# ProProject_Laser_Scanner_Logic_converter.net
KiCad netlist of a schematic drawn in EasyEDA Pro
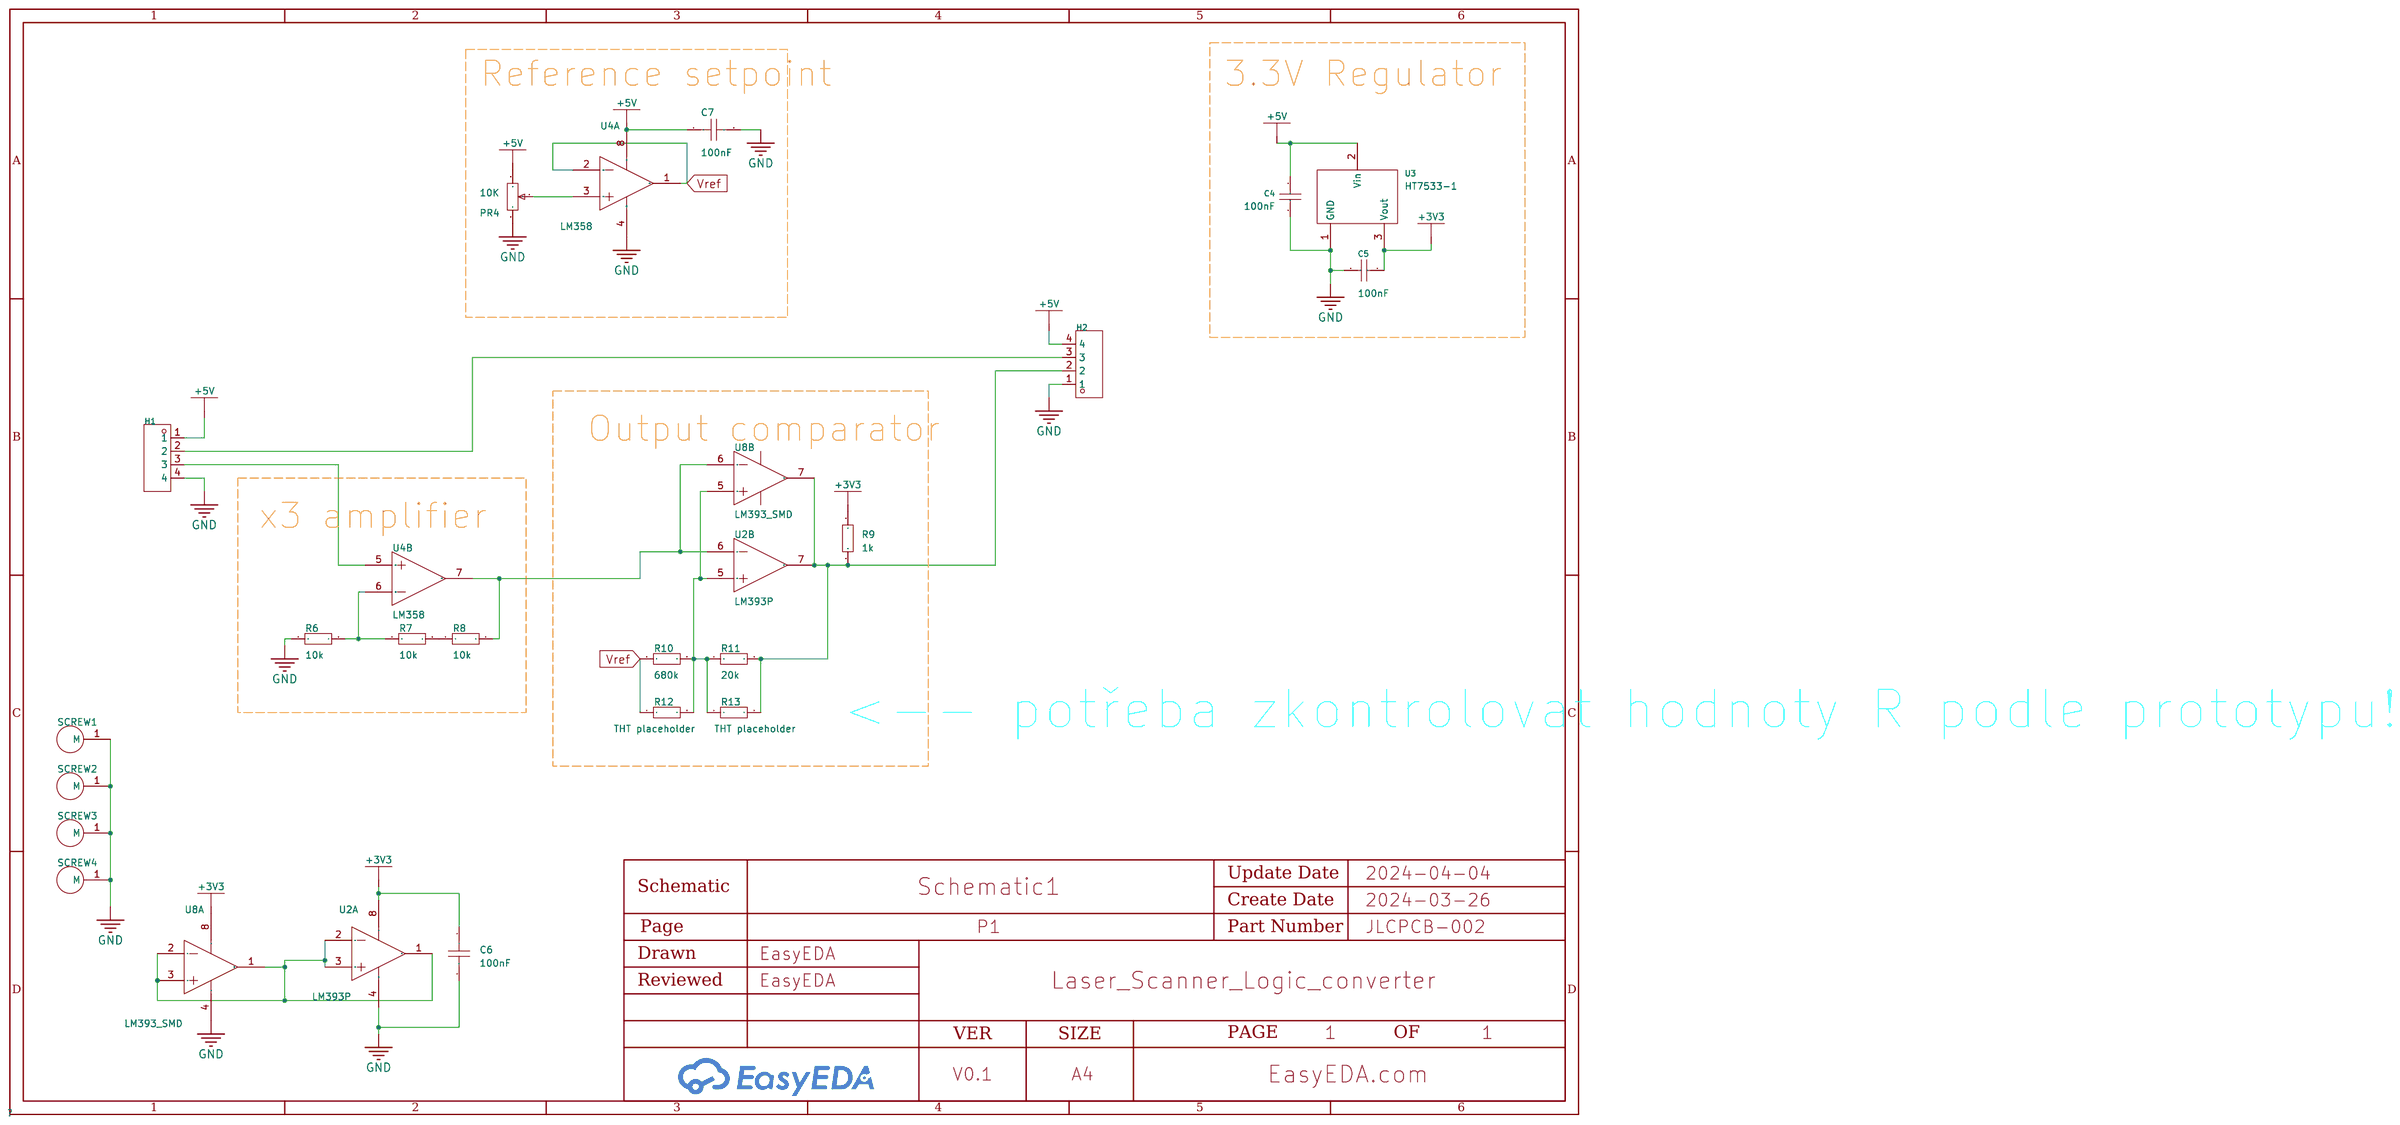
[diagram p0: P1]
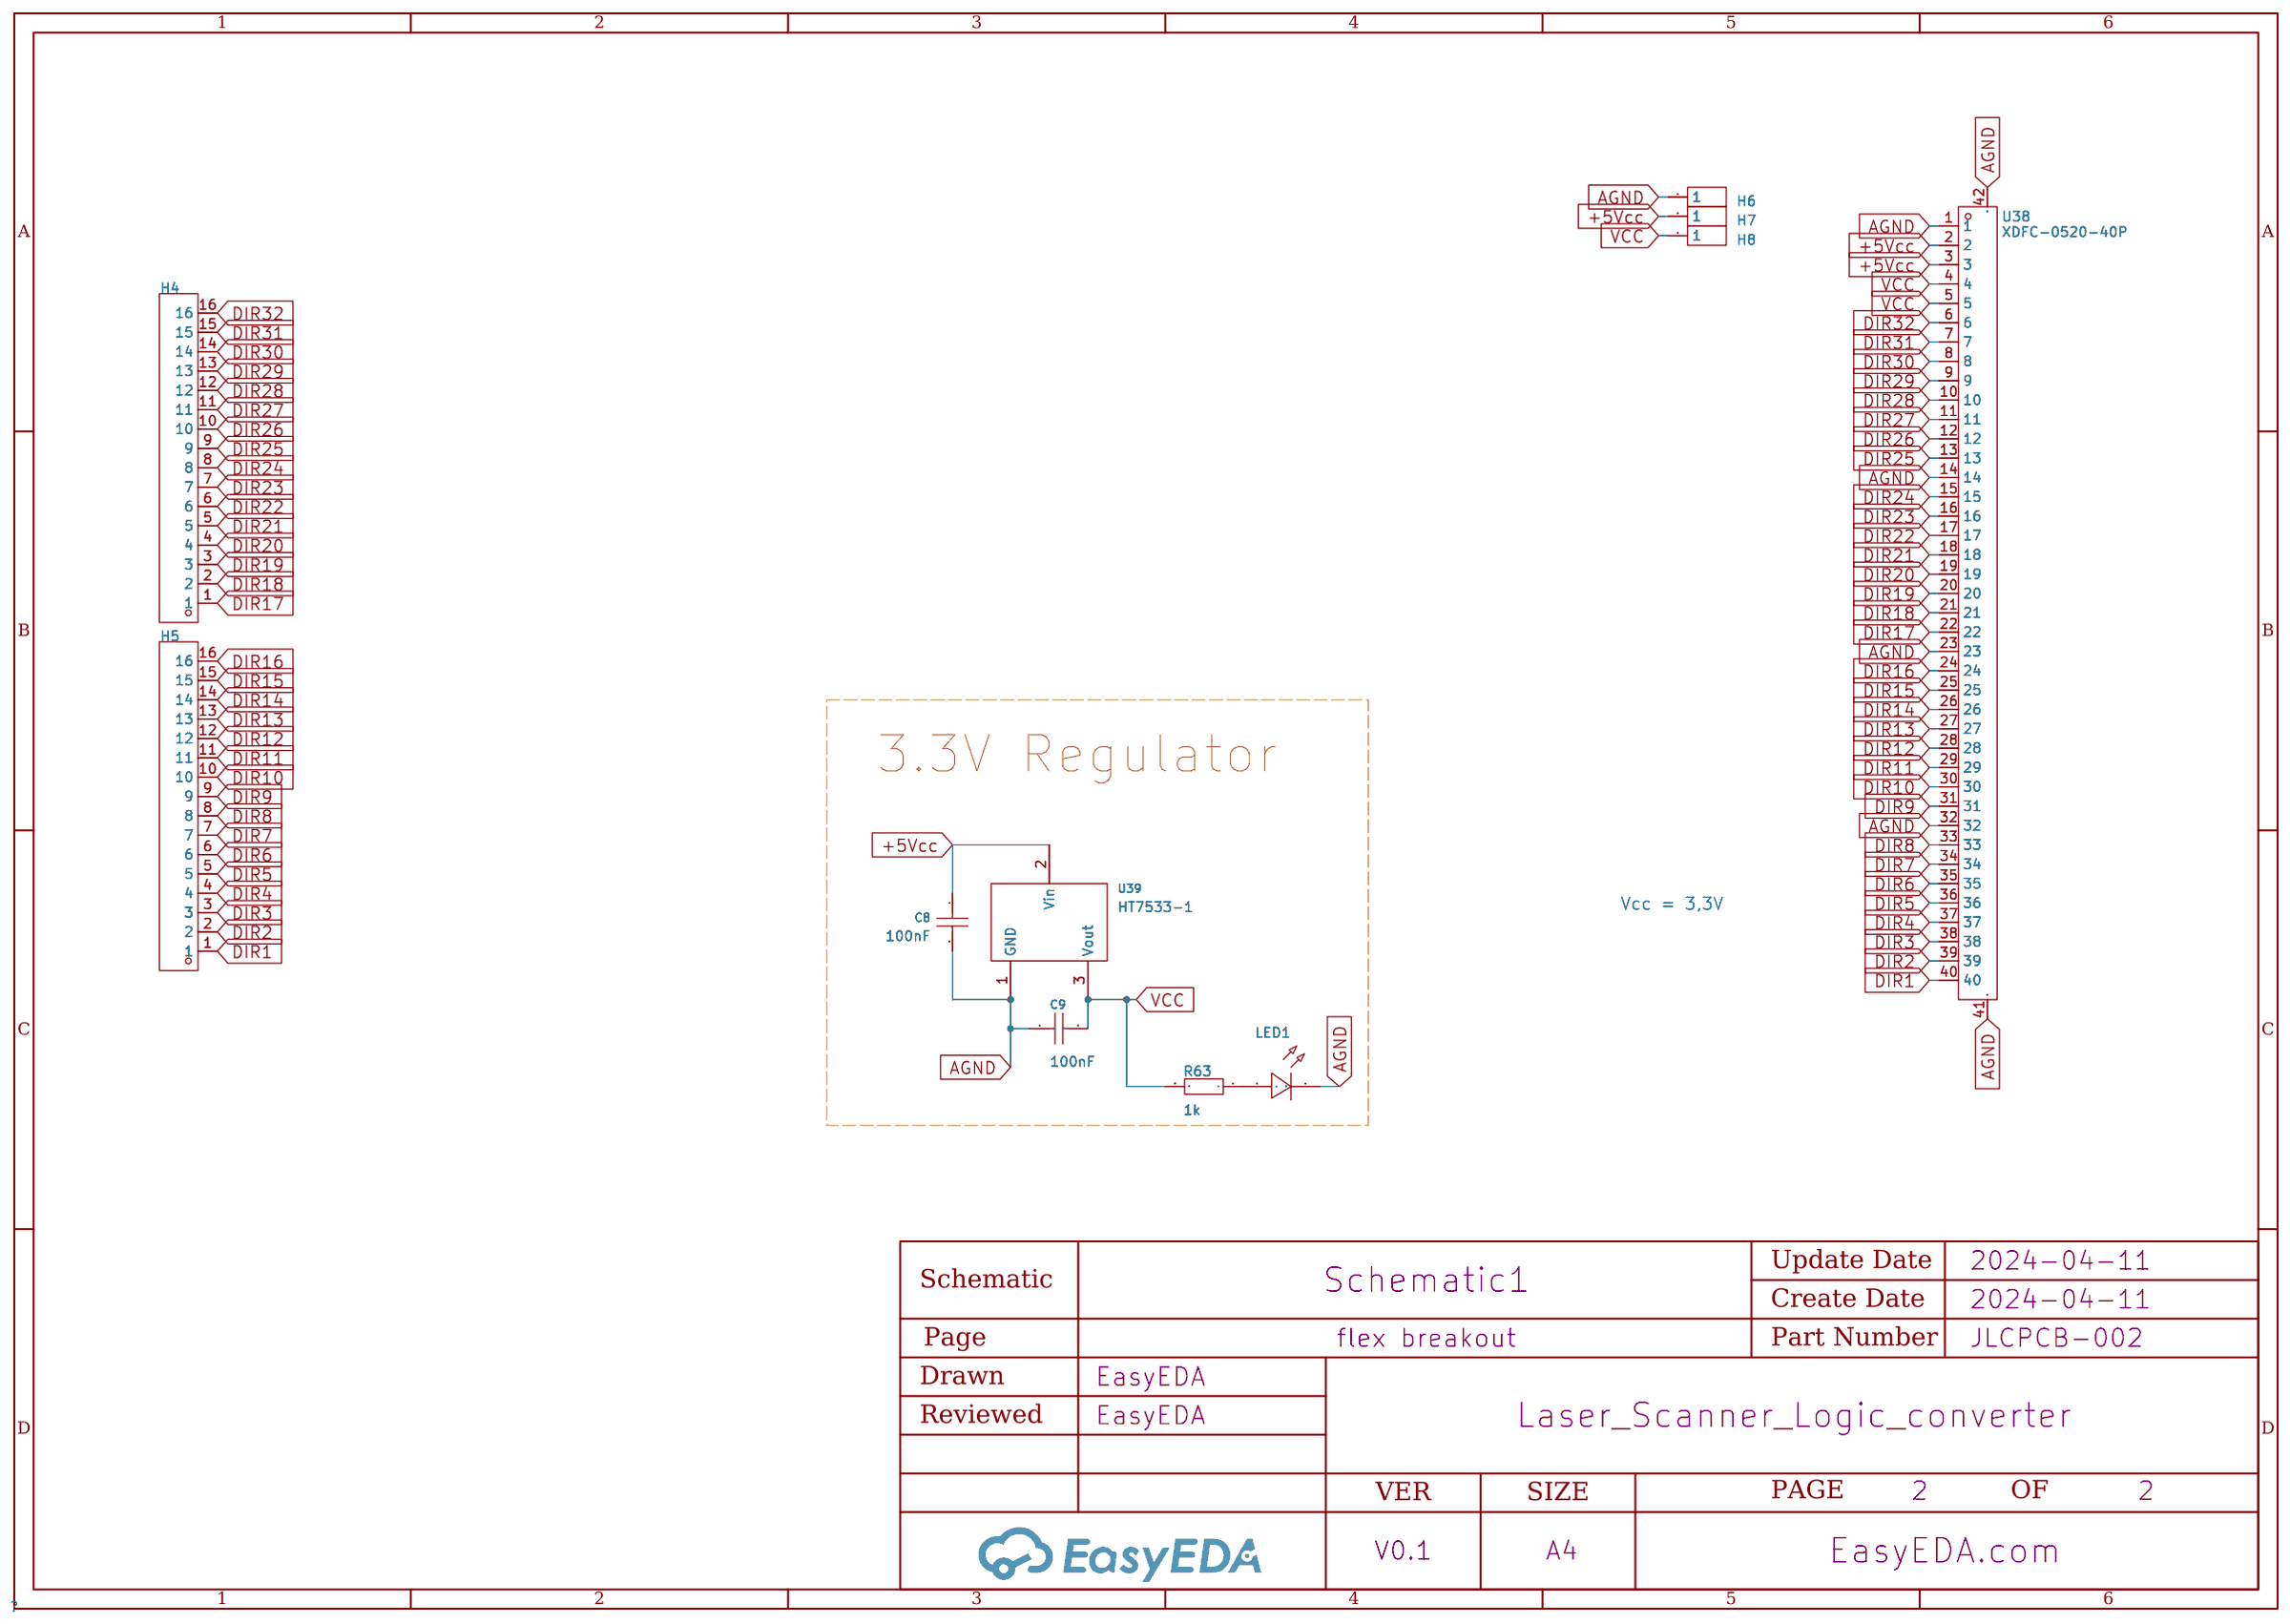
[diagram p1: flex breakout]

(export (version "E")
  (design (tool "Eeschema 10.0.6"))
  (components
    (comp (ref "C4")
      (value "100nF")
      (footprint "easyedapro:C0805")
      (fields
        (field (name "Manufacturer Part") "CL21B105KBFNNNE")
        (field (name "Manufacturer") "SAMSUNG(三星)")
      )
      (libsource (lib "easyedapro") (part "CL21B105KBFNNNE"))
    )
    (comp (ref "C5")
      (value "100nF")
      (footprint "easyedapro:C0805")
      (fields
        (field (name "Manufacturer Part") "CL21B105KBFNNNE")
        (field (name "Manufacturer") "SAMSUNG(三星)")
      )
      (libsource (lib "easyedapro") (part "CL21B105KBFNNNE"))
    )
    (comp (ref "C6")
      (value "100nF")
      (footprint "easyedapro:C0805")
      (libsource (lib "easyedapro") (part "CAP"))
    )
    (comp (ref "C7")
      (value "100nF")
      (footprint "easyedapro:C0805")
      (libsource (lib "easyedapro") (part "CAP"))
    )
    (comp (ref "H1")
      (value "~")
      (footprint "easyedapro:HDR-TH_4P-P2.54-V-F")
      (libsource (lib "easyedapro") (part "2.54-1*4P母"))
    )
    (comp (ref "H2")
      (value "~")
      (footprint "easyedapro:HDR-TH_4P-P2.54-V-F")
      (libsource (lib "easyedapro") (part "2.54-1*4P母"))
    )
    (comp (ref "PR4")
      (value "10K")
      (footprint "easyedapro:RES-ADJ-TH_3P-L9.5-W9.5-P2.54-BR-BS")
      (libsource (lib "easyedapro") (part "3386P-1-103LF"))
    )
    (comp (ref "R6") (value "10k") (footprint "easyedapro:R0603") (libsource (lib "easyedapro") (part "Res")))
    (comp (ref "R7") (value "10k") (footprint "easyedapro:R0603") (libsource (lib "easyedapro") (part "Res")))
    (comp (ref "R8") (value "10k") (footprint "easyedapro:R0603") (libsource (lib "easyedapro") (part "Res")))
    (comp (ref "R9") (value "1k") (footprint "easyedapro:R0603") (libsource (lib "easyedapro") (part "Res")))
    (comp (ref "R10")
      (value "680k")
      (footprint "easyedapro:R0603")
      (libsource (lib "easyedapro") (part "Res"))
    )
    (comp (ref "R11")
      (value "20k")
      (footprint "easyedapro:R0603")
      (libsource (lib "easyedapro") (part "Res"))
    )
    (comp (ref "R12")
      (value "THT placeholder")
      (footprint "easyedapro:R0603")
      (libsource (lib "easyedapro") (part "Res"))
    )
    (comp (ref "R13")
      (value "THT placeholder")
      (footprint "easyedapro:R0603")
      (libsource (lib "easyedapro") (part "Res"))
    )
    (comp (ref "SCREW1")
      (value "~")
      (footprint "easyedapro:M3 MOUNTING HOLE")
      (libsource (lib "easyedapro") (part "MOUNTING HOLE"))
    )
    (comp (ref "SCREW2")
      (value "~")
      (footprint "easyedapro:M3 MOUNTING HOLE")
      (libsource (lib "easyedapro") (part "MOUNTING HOLE"))
    )
    (comp (ref "SCREW3")
      (value "~")
      (footprint "easyedapro:M3 MOUNTING HOLE")
      (libsource (lib "easyedapro") (part "MOUNTING HOLE"))
    )
    (comp (ref "SCREW4")
      (value "~")
      (footprint "easyedapro:M3 MOUNTING HOLE")
      (libsource (lib "easyedapro") (part "MOUNTING HOLE"))
    )
    (comp (ref "U2")
      (value "LM393P")
      (footprint "easyedapro:DIP-8_L10.1-W6.3-P2.54-LS7.6-BL-1")
      (fields (field (name "Manufacturer") "TI(德州仪器)"))
      (libsource (lib "easyedapro") (part "LM393P"))
    )
    (comp (ref "U3")
      (value "HT7533-1")
      (footprint "easyedapro:SOT-89-3_L4.5-W2.5-P1.50-LS4.2-BR")
      (fields (field (name "Manufacturer") "HOLTEK(合泰/盛群)"))
      (libsource (lib "easyedapro") (part "HT7533-1_C14289"))
    )
    (comp (ref "U4")
      (value "LM358")
      (footprint "easyedapro:SOP-8_L4.9-W3.9-P1.27-LS6.0-BL")
      (fields (field (name "Manufacturer") "HX(恒佳兴)"))
      (libsource (lib "easyedapro") (part "LM358_C2984960"))
    )
    (comp (ref "U8")
      (value "LM393_SMD")
      (footprint "easyedapro:SOP-8_L4.9-W3.9-P1.27-LS6.0-BL")
      (fields (field (name "Manufacturer") "IDCHIP(英锐芯)"))
      (libsource (lib "easyedapro") (part "LM393_C400839"))
    )
    (comp (ref "C8")
      (value "100nF")
      (footprint "easyedapro:C0805")
      (fields
        (field (name "Manufacturer Part") "CL21B105KBFNNNE")
        (field (name "Manufacturer") "SAMSUNG(三星)")
      )
      (libsource (lib "easyedapro") (part "CL21B105KBFNNNE"))
    )
    (comp (ref "C9")
      (value "100nF")
      (footprint "easyedapro:C0805")
      (fields
        (field (name "Manufacturer Part") "CL21B105KBFNNNE")
        (field (name "Manufacturer") "SAMSUNG(三星)")
      )
      (libsource (lib "easyedapro") (part "CL21B105KBFNNNE"))
    )
    (comp (ref "H4")
      (value "~")
      (footprint "easyedapro:HDR-TH_16P-P2.54-V-M")
      (libsource (lib "easyedapro") (part "HDR_2.54-1x16P"))
    )
    (comp (ref "H5")
      (value "~")
      (footprint "easyedapro:HDR-TH_16P-P2.54-V-M")
      (libsource (lib "easyedapro") (part "HDR_2.54-1x16P"))
    )
    (comp (ref "H6")
      (value "~")
      (footprint "easyedapro:HDR-TH_1P-V-M_XKB_X4611WV-01I-C28D40")
      (libsource (lib "easyedapro") (part "HDR_1x1"))
    )
    (comp (ref "H7")
      (value "~")
      (footprint "easyedapro:HDR-TH_1P-V-M_XKB_X4611WV-01I-C28D40")
      (libsource (lib "easyedapro") (part "HDR_1x1"))
    )
    (comp (ref "H8")
      (value "~")
      (footprint "easyedapro:HDR-TH_1P-V-M_XKB_X4611WV-01I-C28D40")
      (libsource (lib "easyedapro") (part "HDR_1x1"))
    )
    (comp (ref "LED1")
      (value "~")
      (footprint "easyedapro:LED0805-RD_GREEN")
      (libsource (lib "easyedapro") (part "LED_G"))
    )
    (comp (ref "R63") (value "1k") (footprint "easyedapro:R0603") (libsource (lib "easyedapro") (part "Res")))
    (comp (ref "U38")
      (value "XDFC-0520-40P")
      (footprint "easyedapro:FPC-SMD_40P-P0.50_XDFC-0520-40P")
      (fields (field (name "Manufacturer") "LX(连欣科技)"))
      (libsource (lib "easyedapro") (part "XDFC-0520-40P"))
    )
    (comp (ref "U39")
      (value "HT7533-1")
      (footprint "easyedapro:SOT-89-3_L4.5-W2.5-P1.50-LS4.2-BR")
      (fields (field (name "Manufacturer") "HOLTEK(合泰/盛群)"))
      (libsource (lib "easyedapro") (part "HT7533-1_C14289"))
    )
  )
  (nets
    (net (code "1") (name "+3V3") (class "Default")
      (node (ref "C5") (pin "2") (pinfunction "2_2") (pintype "input"))
      (node (ref "C6") (pin "1") (pinfunction "1_1") (pintype "input"))
      (node (ref "R9") (pin "1") (pinfunction "1_1") (pintype "input"))
      (node (ref "U2") (pin "8") (pinfunction "VCC_8") (pintype "unspecified"))
      (node (ref "U3") (pin "3") (pinfunction "Vout_3") (pintype "input"))
      (node (ref "U8") (pin "8") (pinfunction "VCC_8") (pintype "unspecified"))
    )
    (net (code "2") (name "+5V") (class "Default")
      (node (ref "C4") (pin "1") (pinfunction "1_1") (pintype "input"))
      (node (ref "C7") (pin "1") (pinfunction "1_1") (pintype "input"))
      (node (ref "H1") (pin "1") (pinfunction "1_1") (pintype "input"))
      (node (ref "H2") (pin "4") (pinfunction "4_4") (pintype "input"))
      (node (ref "PR4") (pin "3") (pinfunction "3_3") (pintype "input"))
      (node (ref "U3") (pin "2") (pinfunction "Vin_2") (pintype "input"))
      (node (ref "U4") (pin "8") (pinfunction "Vcc_8") (pintype "unspecified"))
    )
    (net (code "3") (name "+5Vcc") (class "Default")
      (node (ref "C8") (pin "1") (pinfunction "1_1") (pintype "input"))
      (node (ref "H7") (pin "1") (pinfunction "1_1") (pintype "unspecified"))
      (node (ref "U38") (pin "2") (pinfunction "2_2") (pintype "unspecified"))
      (node (ref "U38") (pin "3") (pinfunction "3_3") (pintype "unspecified"))
      (node (ref "U39") (pin "2") (pinfunction "Vin_2") (pintype "input"))
    )
    (net (code "4") (name "AGND") (class "Default")
      (node (ref "C8") (pin "2") (pinfunction "2_2") (pintype "input"))
      (node (ref "C9") (pin "1") (pinfunction "1_1") (pintype "input"))
      (node (ref "H6") (pin "1") (pinfunction "1_1") (pintype "unspecified"))
      (node (ref "LED1") (pin "1") (pinfunction "C_1") (pintype "input"))
      (node (ref "U38") (pin "1") (pinfunction "1_1") (pintype "unspecified"))
      (node (ref "U38") (pin "14") (pinfunction "14_14") (pintype "unspecified"))
      (node (ref "U38") (pin "23") (pinfunction "23_23") (pintype "unspecified"))
      (node (ref "U38") (pin "32") (pinfunction "32_32") (pintype "unspecified"))
      (node (ref "U38") (pin "41") (pinfunction "41_41") (pintype "unspecified"))
      (node (ref "U38") (pin "42") (pinfunction "42_42") (pintype "unspecified"))
      (node (ref "U39") (pin "1") (pinfunction "GND_1") (pintype "input"))
    )
    (net (code "5") (name "DIR1") (class "Default")
      (node (ref "H5") (pin "1") (pinfunction "1_1") (pintype "input"))
      (node (ref "U38") (pin "40") (pinfunction "40_40") (pintype "unspecified"))
    )
    (net (code "6") (name "DIR2") (class "Default")
      (node (ref "H5") (pin "2") (pinfunction "2_2") (pintype "input"))
      (node (ref "U38") (pin "39") (pinfunction "39_39") (pintype "unspecified"))
    )
    (net (code "7") (name "DIR3") (class "Default")
      (node (ref "H5") (pin "3") (pinfunction "3_3") (pintype "input"))
      (node (ref "U38") (pin "38") (pinfunction "38_38") (pintype "unspecified"))
    )
    (net (code "8") (name "DIR4") (class "Default")
      (node (ref "H5") (pin "4") (pinfunction "4_4") (pintype "input"))
      (node (ref "U38") (pin "37") (pinfunction "37_37") (pintype "unspecified"))
    )
    (net (code "9") (name "DIR5") (class "Default")
      (node (ref "H5") (pin "5") (pinfunction "5_5") (pintype "input"))
      (node (ref "U38") (pin "36") (pinfunction "36_36") (pintype "unspecified"))
    )
    (net (code "10") (name "DIR6") (class "Default")
      (node (ref "H5") (pin "6") (pinfunction "6_6") (pintype "input"))
      (node (ref "U38") (pin "35") (pinfunction "35_35") (pintype "unspecified"))
    )
    (net (code "11") (name "DIR7") (class "Default")
      (node (ref "H5") (pin "7") (pinfunction "7_7") (pintype "input"))
      (node (ref "U38") (pin "34") (pinfunction "34_34") (pintype "unspecified"))
    )
    (net (code "12") (name "DIR8") (class "Default")
      (node (ref "H5") (pin "8") (pinfunction "8_8") (pintype "input"))
      (node (ref "U38") (pin "33") (pinfunction "33_33") (pintype "unspecified"))
    )
    (net (code "13") (name "DIR9") (class "Default")
      (node (ref "H5") (pin "9") (pinfunction "9_9") (pintype "input"))
      (node (ref "U38") (pin "31") (pinfunction "31_31") (pintype "unspecified"))
    )
    (net (code "14") (name "DIR10") (class "Default")
      (node (ref "H5") (pin "10") (pinfunction "10_10") (pintype "input"))
      (node (ref "U38") (pin "30") (pinfunction "30_30") (pintype "unspecified"))
    )
    (net (code "15") (name "DIR11") (class "Default")
      (node (ref "H5") (pin "11") (pinfunction "11_11") (pintype "input"))
      (node (ref "U38") (pin "29") (pinfunction "29_29") (pintype "unspecified"))
    )
    (net (code "16") (name "DIR12") (class "Default")
      (node (ref "H5") (pin "12") (pinfunction "12_12") (pintype "input"))
      (node (ref "U38") (pin "28") (pinfunction "28_28") (pintype "unspecified"))
    )
    (net (code "17") (name "DIR13") (class "Default")
      (node (ref "H5") (pin "13") (pinfunction "13_13") (pintype "input"))
      (node (ref "U38") (pin "27") (pinfunction "27_27") (pintype "unspecified"))
    )
    (net (code "18") (name "DIR14") (class "Default")
      (node (ref "H5") (pin "14") (pinfunction "14_14") (pintype "input"))
      (node (ref "U38") (pin "26") (pinfunction "26_26") (pintype "unspecified"))
    )
    (net (code "19") (name "DIR15") (class "Default")
      (node (ref "H5") (pin "15") (pinfunction "15_15") (pintype "input"))
      (node (ref "U38") (pin "25") (pinfunction "25_25") (pintype "unspecified"))
    )
    (net (code "20") (name "DIR16") (class "Default")
      (node (ref "H5") (pin "16") (pinfunction "16_16") (pintype "input"))
      (node (ref "U38") (pin "24") (pinfunction "24_24") (pintype "unspecified"))
    )
    (net (code "21") (name "DIR17") (class "Default")
      (node (ref "H4") (pin "1") (pinfunction "1_1") (pintype "input"))
      (node (ref "U38") (pin "22") (pinfunction "22_22") (pintype "unspecified"))
    )
    (net (code "22") (name "DIR18") (class "Default")
      (node (ref "H4") (pin "2") (pinfunction "2_2") (pintype "input"))
      (node (ref "U38") (pin "21") (pinfunction "21_21") (pintype "unspecified"))
    )
    (net (code "23") (name "DIR19") (class "Default")
      (node (ref "H4") (pin "3") (pinfunction "3_3") (pintype "input"))
      (node (ref "U38") (pin "20") (pinfunction "20_20") (pintype "unspecified"))
    )
    (net (code "24") (name "DIR20") (class "Default")
      (node (ref "H4") (pin "4") (pinfunction "4_4") (pintype "input"))
      (node (ref "U38") (pin "19") (pinfunction "19_19") (pintype "unspecified"))
    )
    (net (code "25") (name "DIR21") (class "Default")
      (node (ref "H4") (pin "5") (pinfunction "5_5") (pintype "input"))
      (node (ref "U38") (pin "18") (pinfunction "18_18") (pintype "unspecified"))
    )
    (net (code "26") (name "DIR22") (class "Default")
      (node (ref "H4") (pin "6") (pinfunction "6_6") (pintype "input"))
      (node (ref "U38") (pin "17") (pinfunction "17_17") (pintype "unspecified"))
    )
    (net (code "27") (name "DIR23") (class "Default")
      (node (ref "H4") (pin "7") (pinfunction "7_7") (pintype "input"))
      (node (ref "U38") (pin "16") (pinfunction "16_16") (pintype "unspecified"))
    )
    (net (code "28") (name "DIR24") (class "Default")
      (node (ref "H4") (pin "8") (pinfunction "8_8") (pintype "input"))
      (node (ref "U38") (pin "15") (pinfunction "15_15") (pintype "unspecified"))
    )
    (net (code "29") (name "DIR25") (class "Default")
      (node (ref "H4") (pin "9") (pinfunction "9_9") (pintype "input"))
      (node (ref "U38") (pin "13") (pinfunction "13_13") (pintype "unspecified"))
    )
    (net (code "30") (name "DIR26") (class "Default")
      (node (ref "H4") (pin "10") (pinfunction "10_10") (pintype "input"))
      (node (ref "U38") (pin "12") (pinfunction "12_12") (pintype "unspecified"))
    )
    (net (code "31") (name "DIR27") (class "Default")
      (node (ref "H4") (pin "11") (pinfunction "11_11") (pintype "input"))
      (node (ref "U38") (pin "11") (pinfunction "11_11") (pintype "unspecified"))
    )
    (net (code "32") (name "DIR28") (class "Default")
      (node (ref "H4") (pin "12") (pinfunction "12_12") (pintype "input"))
      (node (ref "U38") (pin "10") (pinfunction "10_10") (pintype "unspecified"))
    )
    (net (code "33") (name "DIR29") (class "Default")
      (node (ref "H4") (pin "13") (pinfunction "13_13") (pintype "input"))
      (node (ref "U38") (pin "9") (pinfunction "9_9") (pintype "unspecified"))
    )
    (net (code "34") (name "DIR30") (class "Default")
      (node (ref "H4") (pin "14") (pinfunction "14_14") (pintype "input"))
      (node (ref "U38") (pin "8") (pinfunction "8_8") (pintype "unspecified"))
    )
    (net (code "35") (name "DIR31") (class "Default")
      (node (ref "H4") (pin "15") (pinfunction "15_15") (pintype "input"))
      (node (ref "U38") (pin "7") (pinfunction "7_7") (pintype "unspecified"))
    )
    (net (code "36") (name "DIR32") (class "Default")
      (node (ref "H4") (pin "16") (pinfunction "16_16") (pintype "input"))
      (node (ref "U38") (pin "6") (pinfunction "6_6") (pintype "unspecified"))
    )
    (net (code "37") (name "GND") (class "Default")
      (node (ref "C4") (pin "2") (pinfunction "2_2") (pintype "input"))
      (node (ref "C5") (pin "1") (pinfunction "1_1") (pintype "input"))
      (node (ref "C6") (pin "2") (pinfunction "2_2") (pintype "input"))
      (node (ref "C7") (pin "2") (pinfunction "2_2") (pintype "input"))
      (node (ref "H1") (pin "4") (pinfunction "4_4") (pintype "input"))
      (node (ref "H2") (pin "1") (pinfunction "1_1") (pintype "input"))
      (node (ref "PR4") (pin "1") (pinfunction "1_1") (pintype "input"))
      (node (ref "R6") (pin "1") (pinfunction "1_1") (pintype "input"))
      (node (ref "SCREW1") (pin "1") (pinfunction "M_1") (pintype "input"))
      (node (ref "SCREW2") (pin "1") (pinfunction "M_1") (pintype "input"))
      (node (ref "SCREW3") (pin "1") (pinfunction "M_1") (pintype "input"))
      (node (ref "SCREW4") (pin "1") (pinfunction "M_1") (pintype "input"))
      (node (ref "U2") (pin "4") (pinfunction "GND_4") (pintype "unspecified"))
      (node (ref "U3") (pin "1") (pinfunction "GND_1") (pintype "input"))
      (node (ref "U4") (pin "4") (pinfunction "VEE_/_GND_4") (pintype "unspecified"))
      (node (ref "U8") (pin "4") (pinfunction "GND_4") (pintype "unspecified"))
    )
    (net (code "38") (name "Net-(H1-Pad2)") (class "Default")
      (node (ref "H1") (pin "2") (pinfunction "2_2") (pintype "input"))
      (node (ref "H2") (pin "3") (pinfunction "3_3") (pintype "input"))
    )
    (net (code "39") (name "Net-(LED1-A)") (class "Default")
      (node (ref "LED1") (pin "2") (pinfunction "A_2") (pintype "input"))
      (node (ref "R63") (pin "1") (pinfunction "1_1") (pintype "input"))
    )
    (net (code "40") (name "Net-(R7-Pad2)") (class "Default")
      (node (ref "R7") (pin "2") (pinfunction "2_2") (pintype "input"))
      (node (ref "R8") (pin "1") (pinfunction "1_1") (pintype "input"))
    )
    (net (code "41") (name "Net-(U2A-1IN+)") (class "Default")
      (node (ref "U2") (pin "1") (pinfunction "1OUT_1") (pintype "output"))
      (node (ref "U2") (pin "2") (pinfunction "1IN-_2") (pintype "unspecified"))
      (node (ref "U2") (pin "3") (pinfunction "1IN+_3") (pintype "unspecified"))
      (node (ref "U8") (pin "1") (pinfunction "OUTA_1") (pintype "output"))
      (node (ref "U8") (pin "2") (pinfunction "INA-_2") (pintype "unspecified"))
      (node (ref "U8") (pin "3") (pinfunction "INA+_3") (pintype "unspecified"))
    )
    (net (code "42") (name "Net-(U2B-2IN+)") (class "Default")
      (node (ref "R10") (pin "2") (pinfunction "2_2") (pintype "input"))
      (node (ref "R11") (pin "1") (pinfunction "1_1") (pintype "input"))
      (node (ref "R12") (pin "2") (pinfunction "2_2") (pintype "input"))
      (node (ref "R13") (pin "1") (pinfunction "1_1") (pintype "input"))
      (node (ref "U2") (pin "5") (pinfunction "2IN+_5") (pintype "unspecified"))
      (node (ref "U8") (pin "5") (pinfunction "INB+_5") (pintype "unspecified"))
    )
    (net (code "43") (name "Net-(U2B-2IN-)") (class "Default")
      (node (ref "R8") (pin "2") (pinfunction "2_2") (pintype "input"))
      (node (ref "U2") (pin "6") (pinfunction "2IN-_6") (pintype "unspecified"))
      (node (ref "U4") (pin "7") (pinfunction "OUTPUT2_7") (pintype "output"))
      (node (ref "U8") (pin "6") (pinfunction "INB-_6") (pintype "unspecified"))
    )
    (net (code "44") (name "Net-(U2B-2OUT)") (class "Default")
      (node (ref "H2") (pin "2") (pinfunction "2_2") (pintype "input"))
      (node (ref "R11") (pin "2") (pinfunction "2_2") (pintype "input"))
      (node (ref "R13") (pin "2") (pinfunction "2_2") (pintype "input"))
      (node (ref "R9") (pin "2") (pinfunction "2_2") (pintype "input"))
      (node (ref "U2") (pin "7") (pinfunction "2OUT_7") (pintype "output"))
      (node (ref "U8") (pin "7") (pinfunction "OUTB_7") (pintype "output"))
    )
    (net (code "45") (name "Net-(U4A-INPUT1(+))") (class "Default")
      (node (ref "PR4") (pin "2") (pinfunction "2_2") (pintype "input"))
      (node (ref "U4") (pin "3") (pinfunction "INPUT1(+)_3") (pintype "unspecified"))
    )
    (net (code "46") (name "Net-(U4B-INPUT2(+)") (class "Default")
      (node (ref "H1") (pin "3") (pinfunction "3_3") (pintype "input"))
      (node (ref "U4") (pin "5") (pinfunction "INPUT2(+_5") (pintype "unspecified"))
    )
    (net (code "47") (name "Net-(U4B-INPUT2(-))") (class "Default")
      (node (ref "R6") (pin "2") (pinfunction "2_2") (pintype "input"))
      (node (ref "R7") (pin "1") (pinfunction "1_1") (pintype "input"))
      (node (ref "U4") (pin "6") (pinfunction "INPUT2(-)_6") (pintype "unspecified"))
    )
    (net (code "48") (name "VCC") (class "Default")
      (node (ref "C9") (pin "2") (pinfunction "2_2") (pintype "input"))
      (node (ref "H8") (pin "1") (pinfunction "1_1") (pintype "unspecified"))
      (node (ref "R63") (pin "2") (pinfunction "2_2") (pintype "input"))
      (node (ref "U38") (pin "4") (pinfunction "4_4") (pintype "unspecified"))
      (node (ref "U38") (pin "5") (pinfunction "5_5") (pintype "unspecified"))
      (node (ref "U39") (pin "3") (pinfunction "Vout_3") (pintype "input"))
    )
    (net (code "49") (name "Vref") (class "Default")
      (node (ref "R10") (pin "1") (pinfunction "1_1") (pintype "input"))
      (node (ref "R12") (pin "1") (pinfunction "1_1") (pintype "input"))
      (node (ref "U4") (pin "1") (pinfunction "OUTPUT_1_1") (pintype "output"))
      (node (ref "U4") (pin "2") (pinfunction "INPUT1(-)_2") (pintype "unspecified"))
    )
  )
)
